# Diag_586220_Cassette_SMD.net
KiCad netlist of a schematic drawn in EAGLE
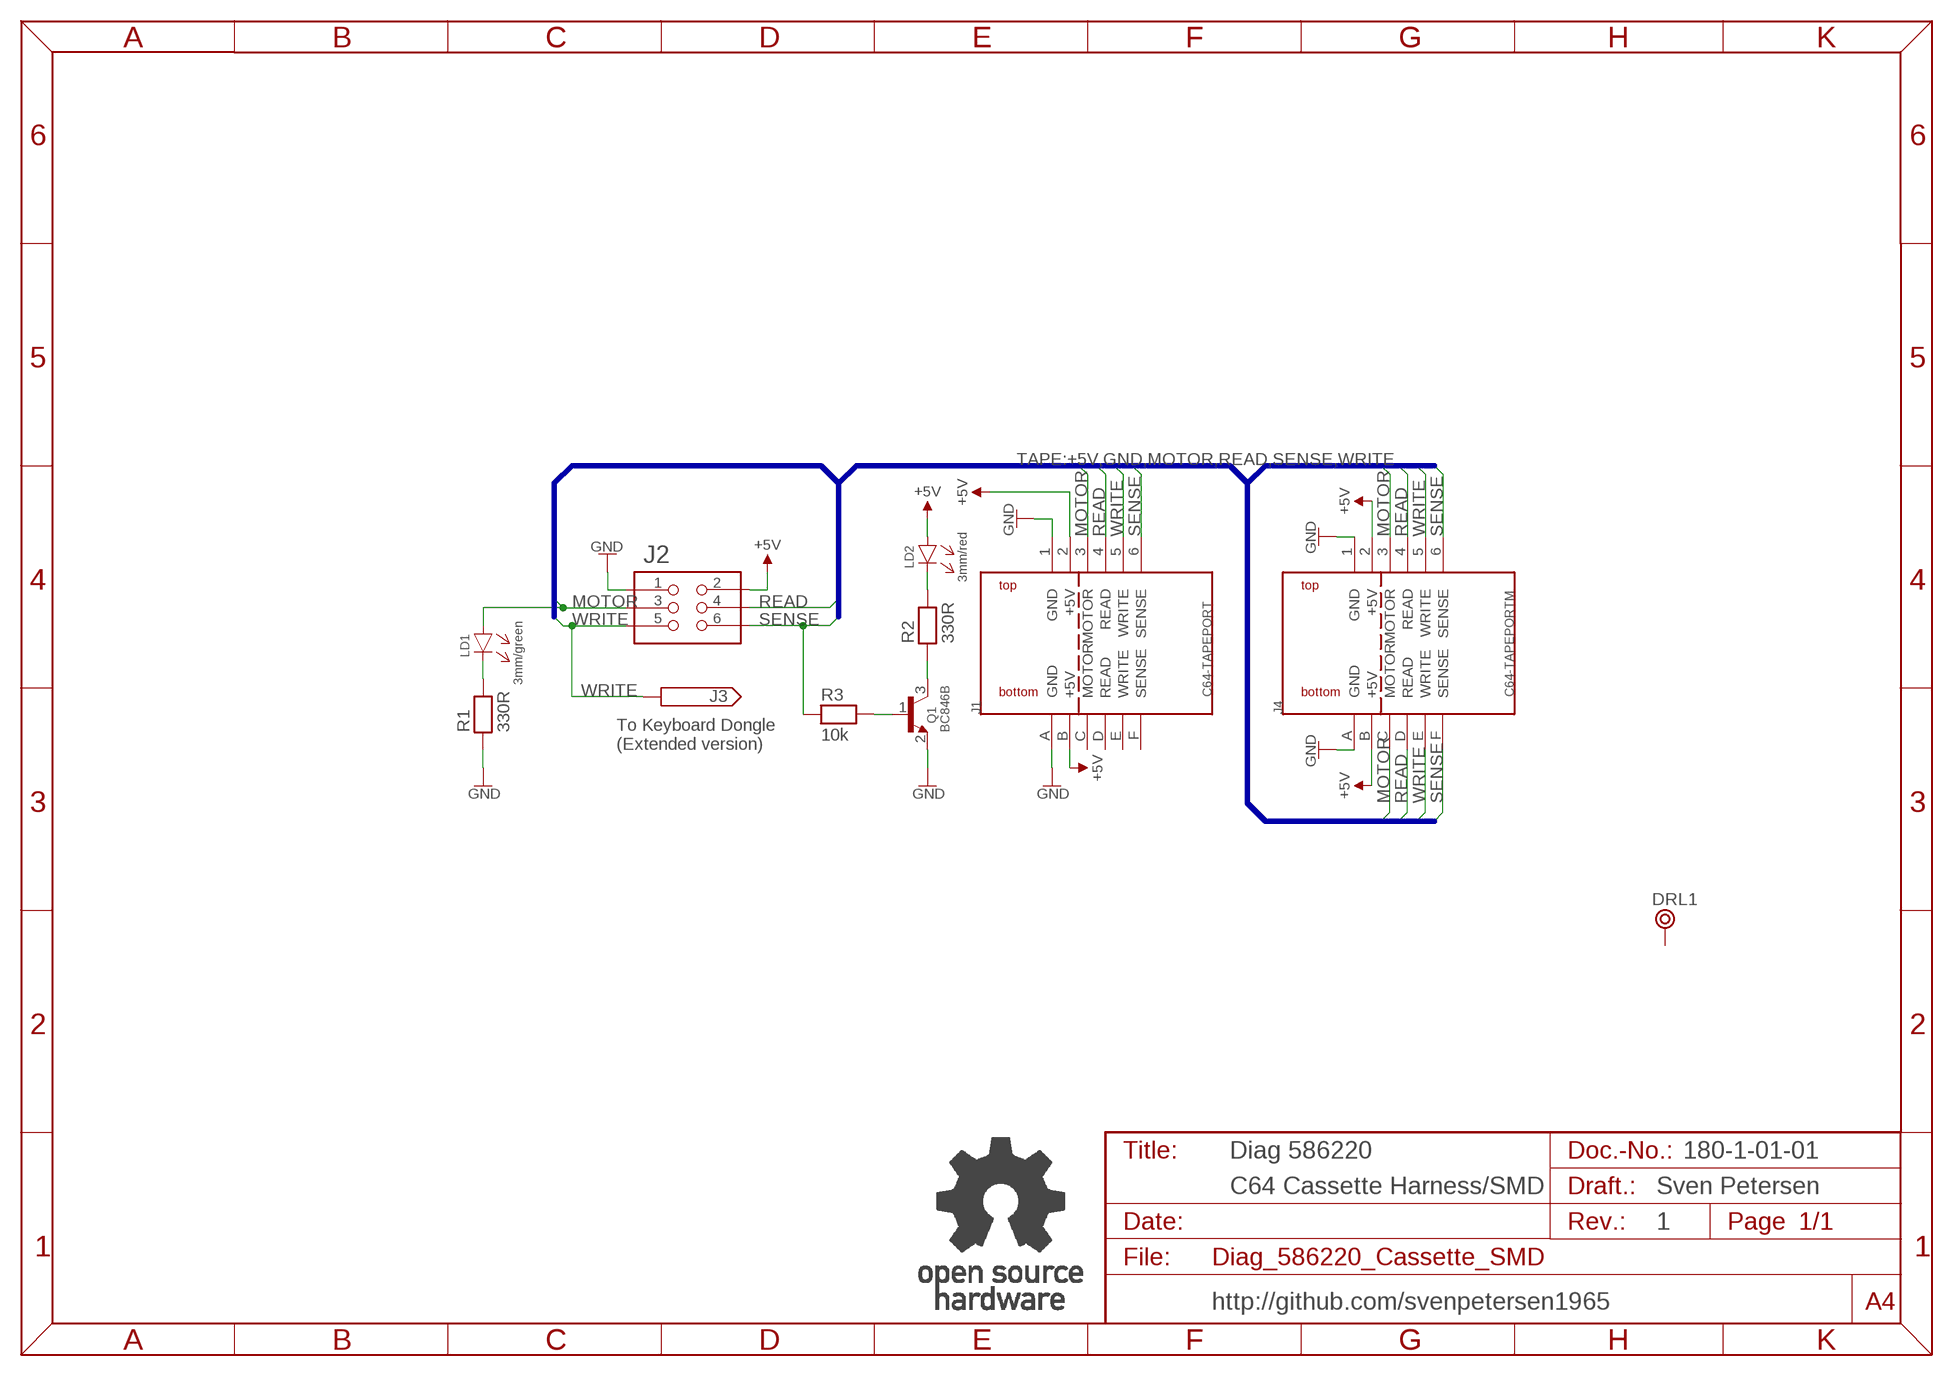
[diagram p0: schematic, sheet 1]

(export (version "E")
  (design (tool "Eeschema 10.0.6"))
  (components
    (comp (ref "DRL1")
      (value "BOHR3,5")
      (footprint "eagle-import:BOHR3,5")
      (libsource (lib "eagle-import") (part "BOHR3,5"))
    )
    (comp (ref "J1")
      (value "C64-TAPEPORT")
      (footprint "eagle-import:TAPEPORT")
      (libsource (lib "eagle-import") (part "C64-TAPEPORT"))
    )
    (comp (ref "J2")
      (value "2X03WV")
      (footprint "eagle-import:2X03WV")
      (libsource (lib "eagle-import") (part "2X03WV"))
    )
    (comp (ref "J3")
      (value "PINHD-1X1")
      (footprint "eagle-import:1X01")
      (libsource (lib "eagle-import") (part "PINHD-1X1"))
    )
    (comp (ref "J4")
      (value "C64-TAPEPORTM")
      (footprint "eagle-import:TAPEPORT_M")
      (libsource (lib "eagle-import") (part "C64-TAPEPORTM"))
    )
    (comp (ref "LD1")
      (value "3mm/green")
      (footprint "eagle-import:3MM")
      (libsource (lib "eagle-import") (part "3MM"))
    )
    (comp (ref "LD2")
      (value "3mm/red")
      (footprint "eagle-import:3MM")
      (libsource (lib "eagle-import") (part "3MM"))
    )
    (comp (ref "Q1")
      (value "BC846B")
      (footprint "eagle-import:SOT23")
      (libsource (lib "eagle-import") (part "BC846"))
    )
    (comp (ref "R1")
      (value "330R")
      (footprint "eagle-import:0805")
      (libsource (lib "eagle-import") (part "RES040805"))
    )
    (comp (ref "R2")
      (value "330R")
      (footprint "eagle-import:0805")
      (libsource (lib "eagle-import") (part "RES040805"))
    )
    (comp (ref "R3")
      (value "10k")
      (footprint "eagle-import:0805")
      (libsource (lib "eagle-import") (part "RES040805"))
    )
    (comp (ref "U$18")
      (value "OPEN_SOURCE_HW")
      (footprint "eagle-import:OPENHW")
      (libsource (lib "eagle-import") (part "OPEN_SOURCE_HW"))
    )
  )
  (nets
    (net (code "2") (name "+5V") (class "Default")
      (node (ref "J1") (pin "2") (pinfunction "+5V_2") (pintype "power_in"))
      (node (ref "J1") (pin "B") (pinfunction "+5V_B") (pintype "power_in"))
      (node (ref "J2") (pin "2") (pinfunction "2_2") (pintype "passive"))
      (node (ref "J4") (pin "2") (pinfunction "+5V_2") (pintype "power_in"))
      (node (ref "J4") (pin "B") (pinfunction "+5V_B") (pintype "power_in"))
      (node (ref "LD2") (pin "A") (pinfunction "A_A") (pintype "bidirectional"))
    )
    (net (code "3") (name "/MOTOR") (class "Default")
      (node (ref "J1") (pin "3") (pinfunction "MOTOR_3") (pintype "output"))
      (node (ref "J2") (pin "3") (pinfunction "3_3") (pintype "passive"))
      (node (ref "J4") (pin "3") (pinfunction "MOTOR_3") (pintype "output"))
      (node (ref "J4") (pin "C") (pinfunction "MOTOR_C") (pintype "output"))
      (node (ref "LD1") (pin "A") (pinfunction "A_A") (pintype "bidirectional"))
    )
    (net (code "4") (name "/READ") (class "Default")
      (node (ref "J1") (pin "4") (pinfunction "READ_4") (pintype "input"))
      (node (ref "J2") (pin "4") (pinfunction "4_4") (pintype "passive"))
      (node (ref "J4") (pin "4") (pinfunction "READ_4") (pintype "input"))
      (node (ref "J4") (pin "D") (pinfunction "READ_D") (pintype "input"))
    )
    (net (code "5") (name "/SENSE") (class "Default")
      (node (ref "J1") (pin "6") (pinfunction "SENSE_6") (pintype "input"))
      (node (ref "J2") (pin "6") (pinfunction "6_6") (pintype "passive"))
      (node (ref "J4") (pin "6") (pinfunction "SENSE_6") (pintype "input"))
      (node (ref "J4") (pin "F") (pinfunction "SENSE_F") (pintype "input"))
      (node (ref "R3") (pin "1") (pinfunction "1_1") (pintype "passive"))
    )
    (net (code "6") (name "/WRITE") (class "Default")
      (node (ref "J1") (pin "5") (pinfunction "WRITE_5") (pintype "output"))
      (node (ref "J2") (pin "5") (pinfunction "5_5") (pintype "passive"))
      (node (ref "J3") (pin "1") (pinfunction "1_1") (pintype "passive"))
      (node (ref "J4") (pin "5") (pinfunction "WRITE_5") (pintype "output"))
      (node (ref "J4") (pin "E") (pinfunction "WRITE_E") (pintype "output"))
    )
    (net (code "8") (name "GND") (class "Default")
      (node (ref "J1") (pin "1") (pinfunction "GND_1") (pintype "power_in"))
      (node (ref "J1") (pin "A") (pinfunction "GND_A") (pintype "power_in"))
      (node (ref "J2") (pin "1") (pinfunction "1_1") (pintype "passive"))
      (node (ref "J4") (pin "1") (pinfunction "GND_1") (pintype "power_in"))
      (node (ref "J4") (pin "A") (pinfunction "GND_A") (pintype "power_in"))
      (node (ref "Q1") (pin "2") (pinfunction "E_2") (pintype "passive"))
      (node (ref "R1") (pin "1") (pinfunction "1_1") (pintype "passive"))
    )
    (net (code "9") (name "Net-(LD1-K)") (class "Default")
      (node (ref "LD1") (pin "C") (pinfunction "K_C") (pintype "bidirectional"))
      (node (ref "R1") (pin "2") (pinfunction "2_2") (pintype "passive"))
    )
    (net (code "10") (name "Net-(LD2-K)") (class "Default")
      (node (ref "LD2") (pin "C") (pinfunction "K_C") (pintype "bidirectional"))
      (node (ref "R2") (pin "2") (pinfunction "2_2") (pintype "passive"))
    )
    (net (code "11") (name "Net-(Q1-B)") (class "Default")
      (node (ref "Q1") (pin "1") (pinfunction "B_1") (pintype "passive"))
      (node (ref "R3") (pin "2") (pinfunction "2_2") (pintype "passive"))
    )
    (net (code "12") (name "Net-(Q1-C)") (class "Default")
      (node (ref "Q1") (pin "3") (pinfunction "C_3") (pintype "passive"))
      (node (ref "R2") (pin "1") (pinfunction "1_1") (pintype "passive"))
    )
    (net (code "13") (name "unconnected-(DRL1-PadP$1)") (class "Default")
      (node (ref "DRL1") (pin "P$1") (pinfunction "P$1_P$1") (pintype "passive"))
    )
    (net (code "14") (name "unconnected-(J1-MOTOR-PadC)") (class "Default")
      (node (ref "J1") (pin "C") (pinfunction "MOTOR_C") (pintype "output"))
    )
    (net (code "15") (name "unconnected-(J1-READ-PadD)") (class "Default")
      (node (ref "J1") (pin "D") (pinfunction "READ_D") (pintype "input"))
    )
    (net (code "16") (name "unconnected-(J1-SENSE-PadF)") (class "Default")
      (node (ref "J1") (pin "F") (pinfunction "SENSE_F") (pintype "input"))
    )
    (net (code "17") (name "unconnected-(J1-WRITE-PadE)") (class "Default")
      (node (ref "J1") (pin "E") (pinfunction "WRITE_E") (pintype "output"))
    )
  )
)
